# hub.net
KiCad netlist of a schematic drawn in EAGLE
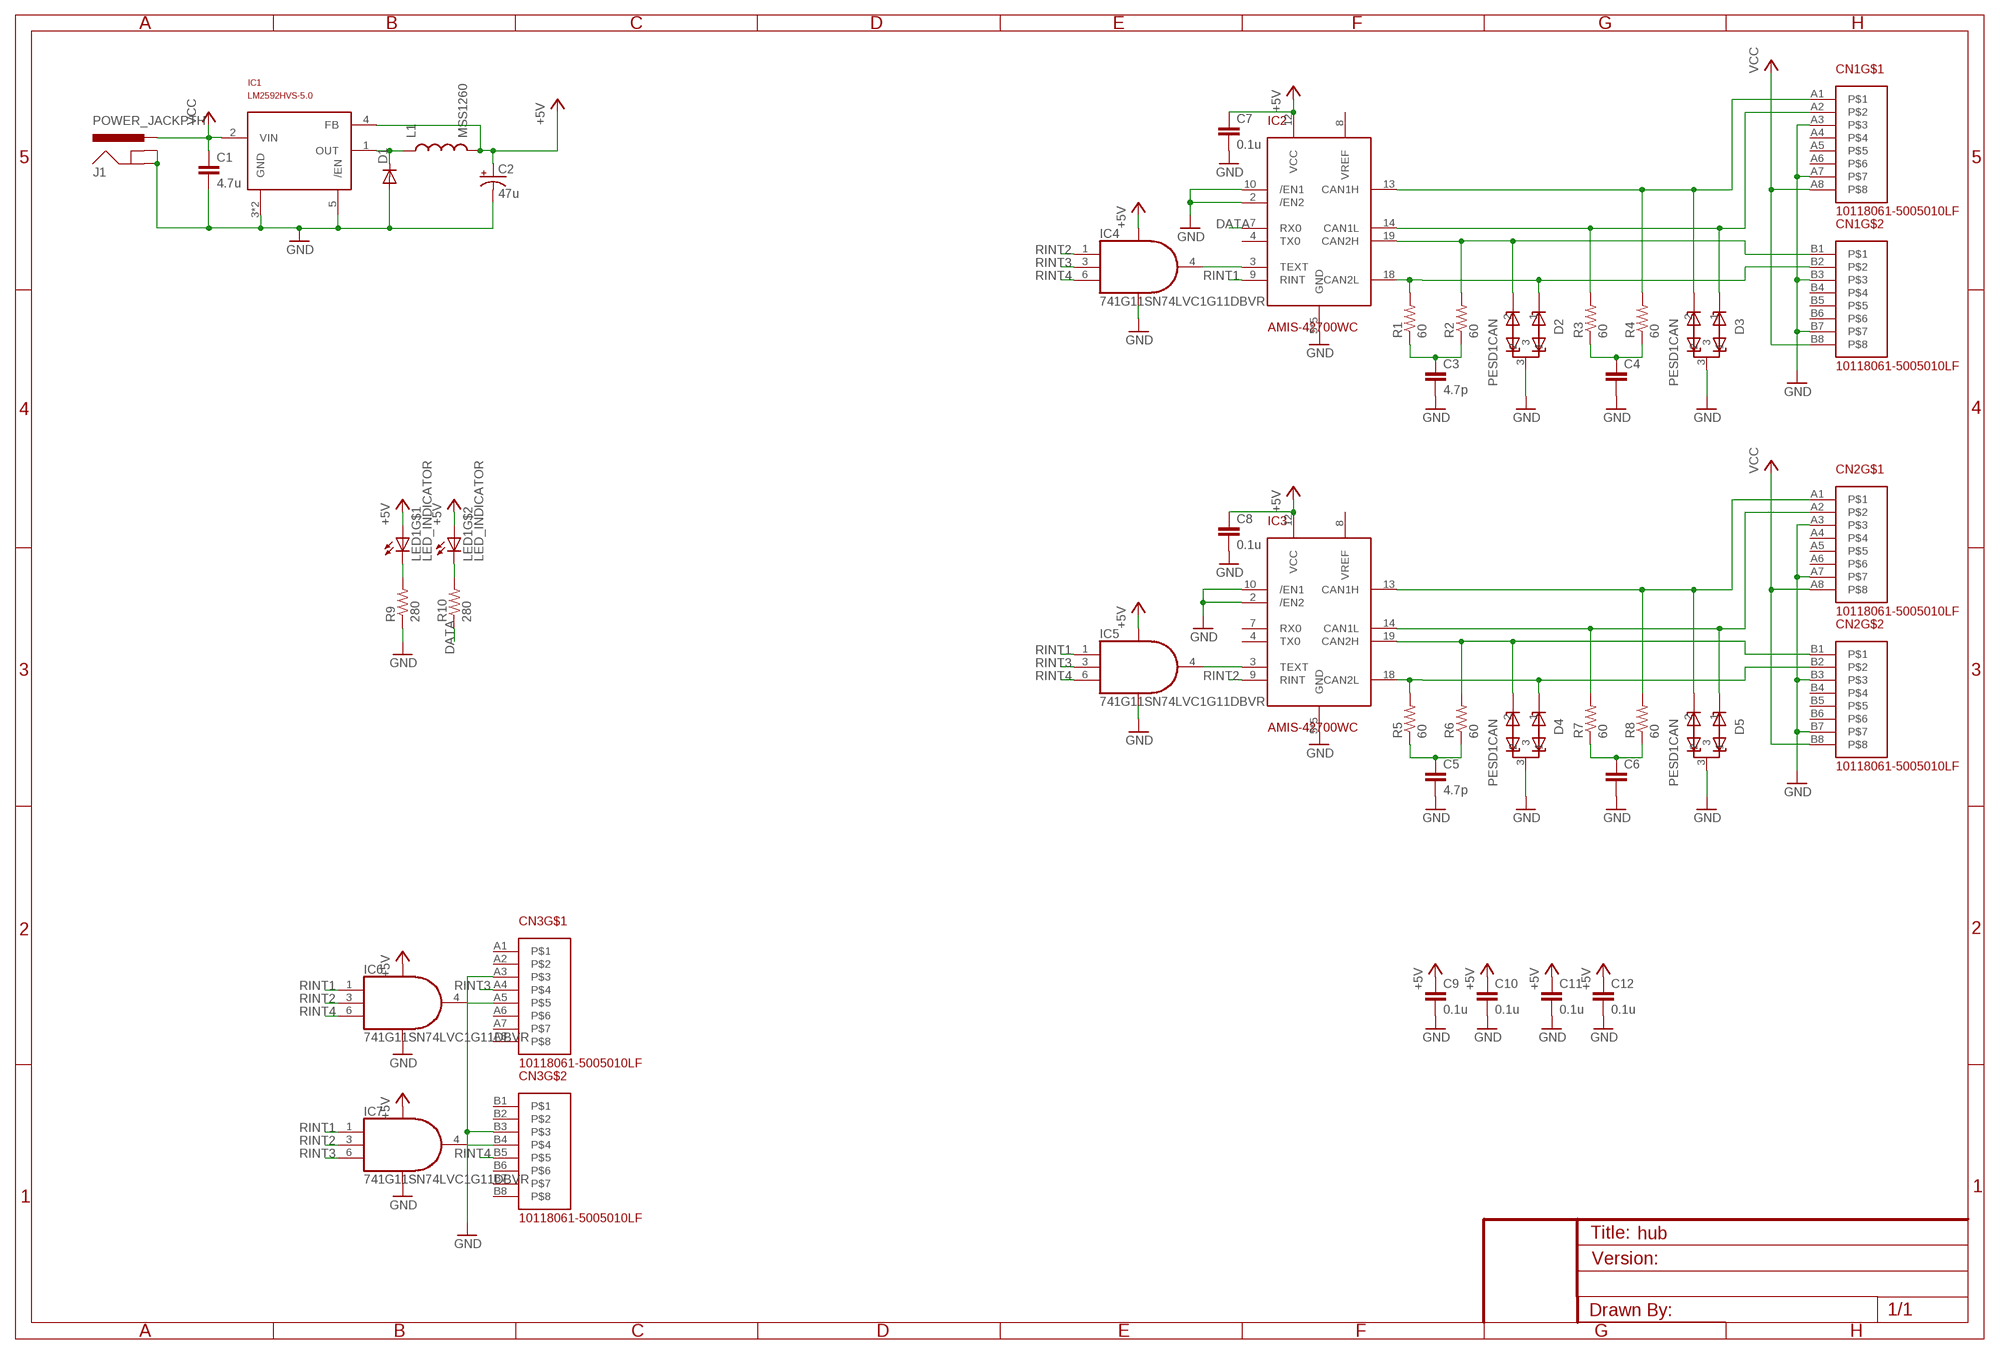
[diagram p0: schematic, sheet 1]

(export (version "E")
  (design (tool "Eeschema 10.0.6"))
  (components
    (comp (ref "C1")
      (value "4.7u")
      (footprint "eagle-import:1206")
      (libsource (lib "eagle-import") (part "CAP1206"))
    )
    (comp (ref "C2")
      (value "47u")
      (footprint "eagle-import:PANASONIC_C")
      (libsource (lib "eagle-import") (part "CAP_POLC"))
    )
    (comp (ref "C3")
      (value "4.7p")
      (footprint "eagle-import:0603-CAP")
      (libsource (lib "eagle-import") (part "SparkFun-Passives_CAP0603-CAP"))
    )
    (comp (ref "C4")
      (value "CAP0603-CAP")
      (footprint "eagle-import:0603-CAP")
      (libsource (lib "eagle-import") (part "SparkFun-Passives_CAP0603-CAP"))
    )
    (comp (ref "C5")
      (value "4.7p")
      (footprint "eagle-import:0603-CAP")
      (libsource (lib "eagle-import") (part "SparkFun-Passives_CAP0603-CAP"))
    )
    (comp (ref "C6")
      (value "CAP0603-CAP")
      (footprint "eagle-import:0603-CAP")
      (libsource (lib "eagle-import") (part "SparkFun-Passives_CAP0603-CAP"))
    )
    (comp (ref "C7")
      (value "0.1u")
      (footprint "eagle-import:0603-CAP")
      (libsource (lib "eagle-import") (part "CAP0603-CAP"))
    )
    (comp (ref "C8")
      (value "0.1u")
      (footprint "eagle-import:0603-CAP")
      (libsource (lib "eagle-import") (part "CAP0603-CAP"))
    )
    (comp (ref "C9")
      (value "0.1u")
      (footprint "eagle-import:0603-CAP")
      (libsource (lib "eagle-import") (part "CAP0603-CAP"))
    )
    (comp (ref "C10")
      (value "0.1u")
      (footprint "eagle-import:0603-CAP")
      (libsource (lib "eagle-import") (part "CAP0603-CAP"))
    )
    (comp (ref "C11")
      (value "0.1u")
      (footprint "eagle-import:0603-CAP")
      (libsource (lib "eagle-import") (part "CAP0603-CAP"))
    )
    (comp (ref "C12")
      (value "0.1u")
      (footprint "eagle-import:0603-CAP")
      (libsource (lib "eagle-import") (part "CAP0603-CAP"))
    )
    (comp (ref "CN1")
      (value "10118061-5005010LF")
      (footprint "eagle-import:10118061")
      (libsource (lib "eagle-import") (part "10118061-5005010LF"))
    )
    (comp (ref "CN2")
      (value "10118061-5005010LF")
      (footprint "eagle-import:10118061")
      (libsource (lib "eagle-import") (part "10118061-5005010LF"))
    )
    (comp (ref "CN3")
      (value "10118061-5005010LF")
      (footprint "eagle-import:10118061")
      (libsource (lib "eagle-import") (part "10118061-5005010LF"))
    )
    (comp (ref "D1")
      (value "DIODESMA-ALT")
      (footprint "eagle-import:SMA-DIODE_ALT")
      (libsource (lib "eagle-import") (part "DIODESMA-ALT"))
    )
    (comp (ref "D2")
      (value "PESD1CAN")
      (footprint "eagle-import:SOT23")
      (libsource (lib "eagle-import") (part "PESD1CAN"))
    )
    (comp (ref "D3")
      (value "PESD1CAN")
      (footprint "eagle-import:SOT23")
      (libsource (lib "eagle-import") (part "PESD1CAN"))
    )
    (comp (ref "D4")
      (value "PESD1CAN")
      (footprint "eagle-import:SOT23")
      (libsource (lib "eagle-import") (part "PESD1CAN"))
    )
    (comp (ref "D5")
      (value "PESD1CAN")
      (footprint "eagle-import:SOT23")
      (libsource (lib "eagle-import") (part "PESD1CAN"))
    )
    (comp (ref "IC1")
      (value "LM2592HVS-5.0")
      (footprint "eagle-import:TO263-5")
      (libsource (lib "eagle-import") (part "LM2595NDH"))
    )
    (comp (ref "IC2")
      (value "AMIS-42700WC")
      (footprint "eagle-import:SO20W")
      (libsource (lib "eagle-import") (part "AMIS-42700WC"))
    )
    (comp (ref "IC3")
      (value "AMIS-42700WC")
      (footprint "eagle-import:SO20W")
      (libsource (lib "eagle-import") (part "AMIS-42700WC"))
    )
    (comp (ref "IC4")
      (value "741G11SN74LVC1G11DBVR")
      (footprint "eagle-import:SOT23-6")
      (libsource (lib "eagle-import") (part "741G11SN74LVC1G11DBVR"))
    )
    (comp (ref "IC5")
      (value "741G11SN74LVC1G11DBVR")
      (footprint "eagle-import:SOT23-6")
      (libsource (lib "eagle-import") (part "741G11SN74LVC1G11DBVR"))
    )
    (comp (ref "IC6")
      (value "741G11SN74LVC1G11DBVR")
      (footprint "eagle-import:SOT23-6")
      (libsource (lib "eagle-import") (part "741G11SN74LVC1G11DBVR"))
    )
    (comp (ref "IC7")
      (value "741G11SN74LVC1G11DBVR")
      (footprint "eagle-import:SOT23-6")
      (libsource (lib "eagle-import") (part "741G11SN74LVC1G11DBVR"))
    )
    (comp (ref "J1")
      (value "POWER_JACKPTH")
      (footprint "eagle-import:POWER_JACK_PTH")
      (libsource (lib "eagle-import") (part "POWER_JACKPTH"))
    )
    (comp (ref "L1")
      (value "MSS1260")
      (footprint "eagle-import:MSS1260")
      (libsource (lib "eagle-import") (part "MSS1260"))
    )
    (comp (ref "LED1")
      (value "LED_INDICATOR")
      (footprint "eagle-import:LED_INDICATOR")
      (libsource (lib "eagle-import") (part "LED_INDICATOR"))
    )
    (comp (ref "R1")
      (value "60")
      (footprint "eagle-import:0603-RES")
      (libsource (lib "eagle-import") (part "RESISTOR0603-RES"))
    )
    (comp (ref "R2")
      (value "60")
      (footprint "eagle-import:0603-RES")
      (libsource (lib "eagle-import") (part "RESISTOR0603-RES"))
    )
    (comp (ref "R3")
      (value "60")
      (footprint "eagle-import:0603-RES")
      (libsource (lib "eagle-import") (part "RESISTOR0603-RES"))
    )
    (comp (ref "R4")
      (value "60")
      (footprint "eagle-import:0603-RES")
      (libsource (lib "eagle-import") (part "RESISTOR0603-RES"))
    )
    (comp (ref "R5")
      (value "60")
      (footprint "eagle-import:0603-RES")
      (libsource (lib "eagle-import") (part "RESISTOR0603-RES"))
    )
    (comp (ref "R6")
      (value "60")
      (footprint "eagle-import:0603-RES")
      (libsource (lib "eagle-import") (part "RESISTOR0603-RES"))
    )
    (comp (ref "R7")
      (value "60")
      (footprint "eagle-import:0603-RES")
      (libsource (lib "eagle-import") (part "RESISTOR0603-RES"))
    )
    (comp (ref "R8")
      (value "60")
      (footprint "eagle-import:0603-RES")
      (libsource (lib "eagle-import") (part "RESISTOR0603-RES"))
    )
    (comp (ref "R9")
      (value "280")
      (footprint "eagle-import:0603-RES")
      (libsource (lib "eagle-import") (part "RESISTOR0603-RES"))
    )
    (comp (ref "R10")
      (value "280")
      (footprint "eagle-import:0603-RES")
      (libsource (lib "eagle-import") (part "RESISTOR0603-RES"))
    )
  )
  (nets
    (net (code "1") (name "+5V") (class "Default")
      (node (ref "C10") (pin "1") (pinfunction "1_1") (pintype "passive"))
      (node (ref "C11") (pin "1") (pinfunction "1_1") (pintype "passive"))
      (node (ref "C12") (pin "1") (pinfunction "1_1") (pintype "passive"))
      (node (ref "C2") (pin "+") (pinfunction "+_+") (pintype "passive"))
      (node (ref "C7") (pin "1") (pinfunction "1_1") (pintype "passive"))
      (node (ref "C8") (pin "1") (pinfunction "1_1") (pintype "passive"))
      (node (ref "C9") (pin "1") (pinfunction "1_1") (pintype "passive"))
      (node (ref "IC1") (pin "4") (pinfunction "FB_4") (pintype "bidirectional"))
      (node (ref "IC2") (pin "12") (pinfunction "VCC_12") (pintype "output"))
      (node (ref "IC3") (pin "12") (pinfunction "VCC_12") (pintype "output"))
      (node (ref "IC4") (pin "5") (pinfunction "VCC_5") (pintype "power_in"))
      (node (ref "IC5") (pin "5") (pinfunction "VCC_5") (pintype "power_in"))
      (node (ref "IC6") (pin "5") (pinfunction "VCC_5") (pintype "power_in"))
      (node (ref "IC7") (pin "5") (pinfunction "VCC_5") (pintype "power_in"))
      (node (ref "L1") (pin "P$2") (pinfunction "2_P$2") (pintype "passive"))
      (node (ref "LED1") (pin "A1") (pinfunction "A_A1") (pintype "passive"))
      (node (ref "LED1") (pin "A2") (pinfunction "A_A2") (pintype "passive"))
    )
    (net (code "2") (name "/DATA") (class "Default")
      (node (ref "IC2") (pin "7") (pinfunction "RX0_7") (pintype "input"))
      (node (ref "R10") (pin "1") (pinfunction "1_1") (pintype "passive"))
    )
    (net (code "3") (name "/RINT1") (class "Default")
      (node (ref "IC2") (pin "9") (pinfunction "RINT_9") (pintype "output"))
      (node (ref "IC5") (pin "1") (pinfunction "I0_1") (pintype "input"))
      (node (ref "IC6") (pin "1") (pinfunction "I0_1") (pintype "input"))
      (node (ref "IC7") (pin "1") (pinfunction "I0_1") (pintype "input"))
    )
    (net (code "4") (name "/RINT2") (class "Default")
      (node (ref "IC3") (pin "9") (pinfunction "RINT_9") (pintype "output"))
      (node (ref "IC4") (pin "1") (pinfunction "I0_1") (pintype "input"))
      (node (ref "IC6") (pin "3") (pinfunction "I1_3") (pintype "input"))
      (node (ref "IC7") (pin "3") (pinfunction "I1_3") (pintype "input"))
    )
    (net (code "5") (name "/RINT3") (class "Default")
      (node (ref "CN3") (pin "A4") (pinfunction "P$4_A4") (pintype "bidirectional"))
      (node (ref "IC4") (pin "3") (pinfunction "I1_3") (pintype "input"))
      (node (ref "IC5") (pin "3") (pinfunction "I1_3") (pintype "input"))
      (node (ref "IC7") (pin "6") (pinfunction "I2_6") (pintype "input"))
    )
    (net (code "6") (name "/RINT4") (class "Default")
      (node (ref "CN3") (pin "B5") (pinfunction "P$5_B5") (pintype "bidirectional"))
      (node (ref "IC4") (pin "6") (pinfunction "I2_6") (pintype "input"))
      (node (ref "IC5") (pin "6") (pinfunction "I2_6") (pintype "input"))
      (node (ref "IC6") (pin "6") (pinfunction "I2_6") (pintype "input"))
    )
    (net (code "7") (name "GND") (class "Default")
      (node (ref "C1") (pin "2") (pinfunction "2_2") (pintype "passive"))
      (node (ref "C10") (pin "2") (pinfunction "2_2") (pintype "passive"))
      (node (ref "C11") (pin "2") (pinfunction "2_2") (pintype "passive"))
      (node (ref "C12") (pin "2") (pinfunction "2_2") (pintype "passive"))
      (node (ref "C2") (pin "-") (pinfunction "-_-") (pintype "passive"))
      (node (ref "C3") (pin "2") (pinfunction "2_2") (pintype "passive"))
      (node (ref "C4") (pin "2") (pinfunction "2_2") (pintype "passive"))
      (node (ref "C5") (pin "2") (pinfunction "2_2") (pintype "passive"))
      (node (ref "C6") (pin "2") (pinfunction "2_2") (pintype "passive"))
      (node (ref "C7") (pin "2") (pinfunction "2_2") (pintype "passive"))
      (node (ref "C8") (pin "2") (pinfunction "2_2") (pintype "passive"))
      (node (ref "C9") (pin "2") (pinfunction "2_2") (pintype "passive"))
      (node (ref "CN1") (pin "A3") (pinfunction "P$3_A3") (pintype "bidirectional"))
      (node (ref "CN1") (pin "A7") (pinfunction "P$7_A7") (pintype "bidirectional"))
      (node (ref "CN1") (pin "B3") (pinfunction "P$3_B3") (pintype "bidirectional"))
      (node (ref "CN1") (pin "B7") (pinfunction "P$7_B7") (pintype "bidirectional"))
      (node (ref "CN2") (pin "A3") (pinfunction "P$3_A3") (pintype "bidirectional"))
      (node (ref "CN2") (pin "A7") (pinfunction "P$7_A7") (pintype "bidirectional"))
      (node (ref "CN2") (pin "B3") (pinfunction "P$3_B3") (pintype "bidirectional"))
      (node (ref "CN2") (pin "B7") (pinfunction "P$7_B7") (pintype "bidirectional"))
      (node (ref "CN3") (pin "A3") (pinfunction "P$3_A3") (pintype "bidirectional"))
      (node (ref "CN3") (pin "B3") (pinfunction "P$3_B3") (pintype "bidirectional"))
      (node (ref "D1") (pin "A") (pinfunction "A_A") (pintype "passive"))
      (node (ref "D2") (pin "3") (pinfunction "3_3") (pintype "bidirectional"))
      (node (ref "D3") (pin "3") (pinfunction "3_3") (pintype "bidirectional"))
      (node (ref "D4") (pin "3") (pinfunction "3_3") (pintype "bidirectional"))
      (node (ref "D5") (pin "3") (pinfunction "3_3") (pintype "bidirectional"))
      (node (ref "IC1") (pin "3") (pinfunction "GND_3") (pintype "bidirectional"))
      (node (ref "IC1") (pin "5") (pinfunction "/EN_5") (pintype "bidirectional"))
      (node (ref "IC1") (pin "6") (pinfunction "GND_6") (pintype "bidirectional"))
      (node (ref "IC2") (pin "10") (pinfunction "/EN1_10") (pintype "input"))
      (node (ref "IC2") (pin "15") (pinfunction "GND_15") (pintype "output"))
      (node (ref "IC2") (pin "16") (pinfunction "GND_16") (pintype "output"))
      (node (ref "IC2") (pin "17") (pinfunction "GND_17") (pintype "output"))
      (node (ref "IC2") (pin "2") (pinfunction "/EN2_2") (pintype "input"))
      (node (ref "IC2") (pin "5") (pinfunction "GND_5") (pintype "output"))
      (node (ref "IC2") (pin "6") (pinfunction "GND_6") (pintype "output"))
      (node (ref "IC3") (pin "10") (pinfunction "/EN1_10") (pintype "input"))
      (node (ref "IC3") (pin "15") (pinfunction "GND_15") (pintype "output"))
      (node (ref "IC3") (pin "16") (pinfunction "GND_16") (pintype "output"))
      (node (ref "IC3") (pin "17") (pinfunction "GND_17") (pintype "output"))
      (node (ref "IC3") (pin "2") (pinfunction "/EN2_2") (pintype "input"))
      (node (ref "IC3") (pin "5") (pinfunction "GND_5") (pintype "output"))
      (node (ref "IC3") (pin "6") (pinfunction "GND_6") (pintype "output"))
      (node (ref "IC4") (pin "2") (pinfunction "GND_2") (pintype "power_in"))
      (node (ref "IC5") (pin "2") (pinfunction "GND_2") (pintype "power_in"))
      (node (ref "IC6") (pin "2") (pinfunction "GND_2") (pintype "power_in"))
      (node (ref "IC7") (pin "2") (pinfunction "GND_2") (pintype "power_in"))
      (node (ref "J1") (pin "GND") (pinfunction "GND_GND") (pintype "bidirectional"))
      (node (ref "J1") (pin "GNDBREAK") (pinfunction "GNDBREAK_GNDBREAK") (pintype "bidirectional"))
      (node (ref "R9") (pin "1") (pinfunction "1_1") (pintype "passive"))
    )
    (net (code "8") (name "Net-(C3-Pad1)") (class "Default")
      (node (ref "C3") (pin "1") (pinfunction "1_1") (pintype "passive"))
      (node (ref "R1") (pin "1") (pinfunction "1_1") (pintype "passive"))
      (node (ref "R2") (pin "1") (pinfunction "1_1") (pintype "passive"))
    )
    (net (code "9") (name "Net-(C4-Pad1)") (class "Default")
      (node (ref "C4") (pin "1") (pinfunction "1_1") (pintype "passive"))
      (node (ref "R3") (pin "1") (pinfunction "1_1") (pintype "passive"))
      (node (ref "R4") (pin "1") (pinfunction "1_1") (pintype "passive"))
    )
    (net (code "10") (name "Net-(C5-Pad1)") (class "Default")
      (node (ref "C5") (pin "1") (pinfunction "1_1") (pintype "passive"))
      (node (ref "R5") (pin "1") (pinfunction "1_1") (pintype "passive"))
      (node (ref "R6") (pin "1") (pinfunction "1_1") (pintype "passive"))
    )
    (net (code "11") (name "Net-(C6-Pad1)") (class "Default")
      (node (ref "C6") (pin "1") (pinfunction "1_1") (pintype "passive"))
      (node (ref "R7") (pin "1") (pinfunction "1_1") (pintype "passive"))
      (node (ref "R8") (pin "1") (pinfunction "1_1") (pintype "passive"))
    )
    (net (code "12") (name "Net-(CN1A-P$1)") (class "Default")
      (node (ref "CN1") (pin "A1") (pinfunction "P$1_A1") (pintype "bidirectional"))
      (node (ref "D3") (pin "2") (pinfunction "2_2") (pintype "bidirectional"))
      (node (ref "IC2") (pin "13") (pinfunction "CAN1H_13") (pintype "output"))
      (node (ref "R4") (pin "2") (pinfunction "2_2") (pintype "passive"))
    )
    (net (code "13") (name "Net-(CN1A-P$2)") (class "Default")
      (node (ref "CN1") (pin "A2") (pinfunction "P$2_A2") (pintype "bidirectional"))
      (node (ref "D3") (pin "1") (pinfunction "1_1") (pintype "bidirectional"))
      (node (ref "IC2") (pin "14") (pinfunction "CAN1L_14") (pintype "output"))
      (node (ref "R3") (pin "2") (pinfunction "2_2") (pintype "passive"))
    )
    (net (code "14") (name "Net-(CN1B-P$1)") (class "Default")
      (node (ref "CN1") (pin "B1") (pinfunction "P$1_B1") (pintype "bidirectional"))
      (node (ref "D2") (pin "2") (pinfunction "2_2") (pintype "bidirectional"))
      (node (ref "IC2") (pin "19") (pinfunction "CAN2H_19") (pintype "output"))
      (node (ref "R2") (pin "2") (pinfunction "2_2") (pintype "passive"))
    )
    (net (code "15") (name "Net-(CN1B-P$2)") (class "Default")
      (node (ref "CN1") (pin "B2") (pinfunction "P$2_B2") (pintype "bidirectional"))
      (node (ref "D2") (pin "1") (pinfunction "1_1") (pintype "bidirectional"))
      (node (ref "IC2") (pin "18") (pinfunction "CAN2L_18") (pintype "output"))
      (node (ref "R1") (pin "2") (pinfunction "2_2") (pintype "passive"))
    )
    (net (code "16") (name "Net-(CN2A-P$1)") (class "Default")
      (node (ref "CN2") (pin "A1") (pinfunction "P$1_A1") (pintype "bidirectional"))
      (node (ref "D5") (pin "2") (pinfunction "2_2") (pintype "bidirectional"))
      (node (ref "IC3") (pin "13") (pinfunction "CAN1H_13") (pintype "output"))
      (node (ref "R8") (pin "2") (pinfunction "2_2") (pintype "passive"))
    )
    (net (code "17") (name "Net-(CN2A-P$2)") (class "Default")
      (node (ref "CN2") (pin "A2") (pinfunction "P$2_A2") (pintype "bidirectional"))
      (node (ref "D5") (pin "1") (pinfunction "1_1") (pintype "bidirectional"))
      (node (ref "IC3") (pin "14") (pinfunction "CAN1L_14") (pintype "output"))
      (node (ref "R7") (pin "2") (pinfunction "2_2") (pintype "passive"))
    )
    (net (code "18") (name "Net-(CN2B-P$1)") (class "Default")
      (node (ref "CN2") (pin "B1") (pinfunction "P$1_B1") (pintype "bidirectional"))
      (node (ref "D4") (pin "2") (pinfunction "2_2") (pintype "bidirectional"))
      (node (ref "IC3") (pin "19") (pinfunction "CAN2H_19") (pintype "output"))
      (node (ref "R6") (pin "2") (pinfunction "2_2") (pintype "passive"))
    )
    (net (code "19") (name "Net-(CN2B-P$2)") (class "Default")
      (node (ref "CN2") (pin "B2") (pinfunction "P$2_B2") (pintype "bidirectional"))
      (node (ref "D4") (pin "1") (pinfunction "1_1") (pintype "bidirectional"))
      (node (ref "IC3") (pin "18") (pinfunction "CAN2L_18") (pintype "output"))
      (node (ref "R5") (pin "2") (pinfunction "2_2") (pintype "passive"))
    )
    (net (code "20") (name "Net-(CN3A-P$5)") (class "Default")
      (node (ref "CN3") (pin "A5") (pinfunction "P$5_A5") (pintype "bidirectional"))
      (node (ref "IC6") (pin "4") (pinfunction "O_4") (pintype "output"))
    )
    (net (code "21") (name "Net-(CN3B-P$4)") (class "Default")
      (node (ref "CN3") (pin "B4") (pinfunction "P$4_B4") (pintype "bidirectional"))
      (node (ref "IC7") (pin "4") (pinfunction "O_4") (pintype "output"))
    )
    (net (code "22") (name "Net-(IC1-OUT)") (class "Default")
      (node (ref "D1") (pin "C") (pinfunction "C_C") (pintype "passive"))
      (node (ref "IC1") (pin "1") (pinfunction "OUT_1") (pintype "bidirectional"))
      (node (ref "L1") (pin "P$1") (pinfunction "1_P$1") (pintype "passive"))
    )
    (net (code "23") (name "Net-(IC2-TEXT)") (class "Default")
      (node (ref "IC2") (pin "3") (pinfunction "TEXT_3") (pintype "input"))
      (node (ref "IC4") (pin "4") (pinfunction "O_4") (pintype "output"))
    )
    (net (code "24") (name "Net-(IC3-TEXT)") (class "Default")
      (node (ref "IC3") (pin "3") (pinfunction "TEXT_3") (pintype "input"))
      (node (ref "IC5") (pin "4") (pinfunction "O_4") (pintype "output"))
    )
    (net (code "25") (name "Net-(LED1A-C)") (class "Default")
      (node (ref "LED1") (pin "C1") (pinfunction "C_C1") (pintype "passive"))
      (node (ref "R9") (pin "2") (pinfunction "2_2") (pintype "passive"))
    )
    (net (code "26") (name "Net-(LED1B-C)") (class "Default")
      (node (ref "LED1") (pin "C2") (pinfunction "C_C2") (pintype "passive"))
      (node (ref "R10") (pin "2") (pinfunction "2_2") (pintype "passive"))
    )
    (net (code "27") (name "VCC") (class "Default")
      (node (ref "C1") (pin "1") (pinfunction "1_1") (pintype "passive"))
      (node (ref "CN1") (pin "A8") (pinfunction "P$8_A8") (pintype "bidirectional"))
      (node (ref "CN1") (pin "B8") (pinfunction "P$8_B8") (pintype "bidirectional"))
      (node (ref "CN2") (pin "A8") (pinfunction "P$8_A8") (pintype "bidirectional"))
      (node (ref "CN2") (pin "B8") (pinfunction "P$8_B8") (pintype "bidirectional"))
      (node (ref "IC1") (pin "2") (pinfunction "VIN_2") (pintype "bidirectional"))
      (node (ref "J1") (pin "PWR") (pinfunction "PWR_PWR") (pintype "bidirectional"))
    )
    (net (code "28") (name "unconnected-(CN1A-P$4-PadA4)") (class "Default")
      (node (ref "CN1") (pin "A4") (pinfunction "P$4_A4") (pintype "bidirectional"))
    )
    (net (code "29") (name "unconnected-(CN1A-P$5-PadA5)") (class "Default")
      (node (ref "CN1") (pin "A5") (pinfunction "P$5_A5") (pintype "bidirectional"))
    )
    (net (code "30") (name "unconnected-(CN1A-P$6-PadA6)") (class "Default")
      (node (ref "CN1") (pin "A6") (pinfunction "P$6_A6") (pintype "bidirectional"))
    )
    (net (code "31") (name "unconnected-(CN1B-P$4-PadB4)") (class "Default")
      (node (ref "CN1") (pin "B4") (pinfunction "P$4_B4") (pintype "bidirectional"))
    )
    (net (code "32") (name "unconnected-(CN1B-P$5-PadB5)") (class "Default")
      (node (ref "CN1") (pin "B5") (pinfunction "P$5_B5") (pintype "bidirectional"))
    )
    (net (code "33") (name "unconnected-(CN1B-P$6-PadB6)") (class "Default")
      (node (ref "CN1") (pin "B6") (pinfunction "P$6_B6") (pintype "bidirectional"))
    )
    (net (code "34") (name "unconnected-(CN2A-P$4-PadA4)") (class "Default")
      (node (ref "CN2") (pin "A4") (pinfunction "P$4_A4") (pintype "bidirectional"))
    )
    (net (code "35") (name "unconnected-(CN2A-P$5-PadA5)") (class "Default")
      (node (ref "CN2") (pin "A5") (pinfunction "P$5_A5") (pintype "bidirectional"))
    )
    (net (code "36") (name "unconnected-(CN2A-P$6-PadA6)") (class "Default")
      (node (ref "CN2") (pin "A6") (pinfunction "P$6_A6") (pintype "bidirectional"))
    )
    (net (code "37") (name "unconnected-(CN2B-P$4-PadB4)") (class "Default")
      (node (ref "CN2") (pin "B4") (pinfunction "P$4_B4") (pintype "bidirectional"))
    )
    (net (code "38") (name "unconnected-(CN2B-P$5-PadB5)") (class "Default")
      (node (ref "CN2") (pin "B5") (pinfunction "P$5_B5") (pintype "bidirectional"))
    )
    (net (code "39") (name "unconnected-(CN2B-P$6-PadB6)") (class "Default")
      (node (ref "CN2") (pin "B6") (pinfunction "P$6_B6") (pintype "bidirectional"))
    )
    (net (code "40") (name "unconnected-(CN3A-P$1-PadA1)") (class "Default")
      (node (ref "CN3") (pin "A1") (pinfunction "P$1_A1") (pintype "bidirectional"))
    )
    (net (code "41") (name "unconnected-(CN3A-P$2-PadA2)") (class "Default")
      (node (ref "CN3") (pin "A2") (pinfunction "P$2_A2") (pintype "bidirectional"))
    )
    (net (code "42") (name "unconnected-(CN3A-P$6-PadA6)") (class "Default")
      (node (ref "CN3") (pin "A6") (pinfunction "P$6_A6") (pintype "bidirectional"))
    )
    (net (code "43") (name "unconnected-(CN3A-P$7-PadA7)") (class "Default")
      (node (ref "CN3") (pin "A7") (pinfunction "P$7_A7") (pintype "bidirectional"))
    )
    (net (code "44") (name "unconnected-(CN3A-P$8-PadA8)") (class "Default")
      (node (ref "CN3") (pin "A8") (pinfunction "P$8_A8") (pintype "bidirectional"))
    )
    (net (code "45") (name "unconnected-(CN3B-P$1-PadB1)") (class "Default")
      (node (ref "CN3") (pin "B1") (pinfunction "P$1_B1") (pintype "bidirectional"))
    )
    (net (code "46") (name "unconnected-(CN3B-P$2-PadB2)") (class "Default")
      (node (ref "CN3") (pin "B2") (pinfunction "P$2_B2") (pintype "bidirectional"))
    )
    (net (code "47") (name "unconnected-(CN3B-P$6-PadB6)") (class "Default")
      (node (ref "CN3") (pin "B6") (pinfunction "P$6_B6") (pintype "bidirectional"))
    )
    (net (code "48") (name "unconnected-(CN3B-P$7-PadB7)") (class "Default")
      (node (ref "CN3") (pin "B7") (pinfunction "P$7_B7") (pintype "bidirectional"))
    )
    (net (code "49") (name "unconnected-(CN3B-P$8-PadB8)") (class "Default")
      (node (ref "CN3") (pin "B8") (pinfunction "P$8_B8") (pintype "bidirectional"))
    )
    (net (code "50") (name "unconnected-(IC2-TX0-Pad4)") (class "Default")
      (node (ref "IC2") (pin "4") (pinfunction "TX0_4") (pintype "output"))
    )
    (net (code "51") (name "unconnected-(IC2-VREF-Pad8)") (class "Default")
      (node (ref "IC2") (pin "8") (pinfunction "VREF_8") (pintype "output"))
    )
    (net (code "52") (name "unconnected-(IC3-RX0-Pad7)") (class "Default")
      (node (ref "IC3") (pin "7") (pinfunction "RX0_7") (pintype "input"))
    )
    (net (code "53") (name "unconnected-(IC3-TX0-Pad4)") (class "Default")
      (node (ref "IC3") (pin "4") (pinfunction "TX0_4") (pintype "output"))
    )
    (net (code "54") (name "unconnected-(IC3-VREF-Pad8)") (class "Default")
      (node (ref "IC3") (pin "8") (pinfunction "VREF_8") (pintype "output"))
    )
  )
)
